# Porsche_Brake_Light.net
KiCad netlist of a schematic drawn in Altium Designer
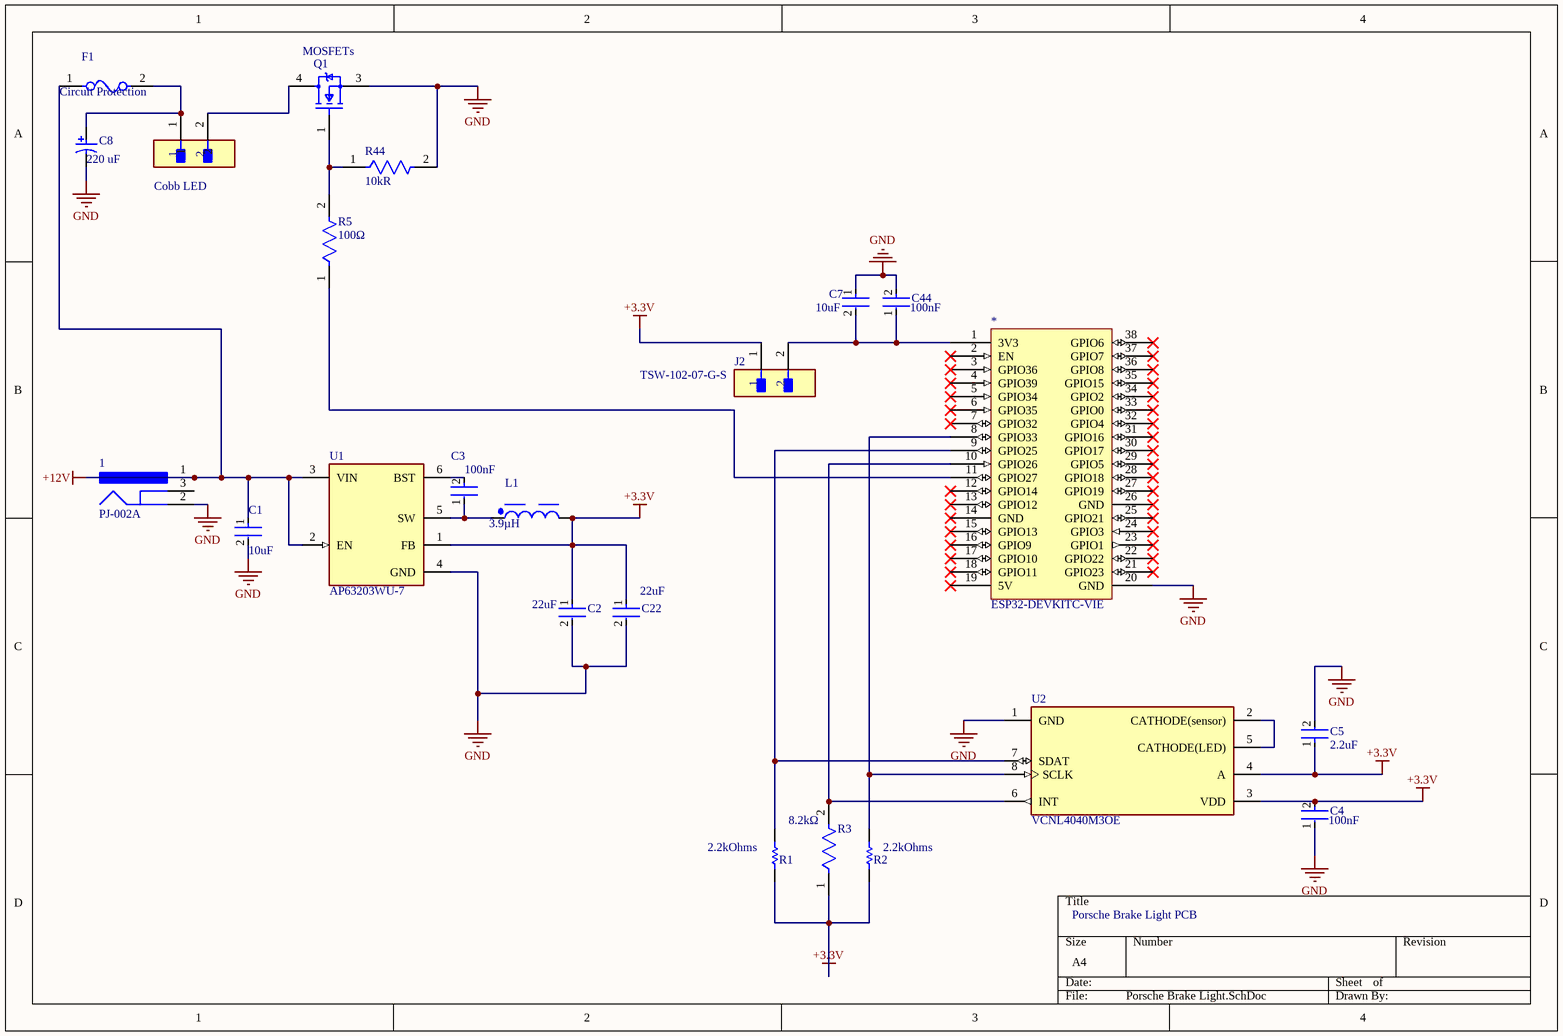
[diagram p0: Porsche Brake Light.SchDoc]

(export (version "E")
  (design (tool "Eeschema 10.0.6"))
  (components
    (comp (ref "*")
      (value "ESP32-DEVKITC-VIE")
      (footprint "ESP32-DEVKITC-VIE-Footprint-1")
      (libsource (lib "Altium DX") (part "ESP32-DEVKITC-VIE-Symbol-1"))
    )
    (comp (ref "1")
      (value "PJ-002A")
      (footprint "CUI-PJ-002A_V")
      (fields (field (name "MANUFACTURER") "CUIInc."))
      (libsource (lib "Altium Content Vault") (part "JACK-2CD3-RN_B"))
    )
    (comp (ref "C1")
      (value "GRM21BR61E106KA73L")
      (footprint "FP-GRM21B-0_15-IPC_C")
      (description "Chip Multilayer Ceramic Capacitors for General Purpose, 0805, 10uF, X5R, 15%, 10%, 25V")
      (fields
        (field (name "VOLTAGE") "25V")
        (field (name "CAPACITANCE") "10uF")
        (field (name "TOLERANCE") "10%")
      )
      (libsource (lib "Altium Content Vault") (part "b4654b650e69147ec39a6b967a45e02"))
    )
    (comp (ref "C2")
      (value "GRM21BZ71A226ME15L")
      (footprint "FP-GRM21B-0_2-e0_2_0_7-IPC_B")
      (description "Chip Multilayer Ceramic Capacitors for General Purpose, 0805, 22uF, X7R, 15%, 20%, 10V")
      (libsource (lib "Altium Content Vault") (part "b4654b650e69147ec39a6b967a45e02"))
    )
    (comp (ref "C3")
      (value "C1608X7R1E104K080AA")
      (footprint "FP-C1608-080-0_1-IPC_B")
      (description "Multilayer Ceramic Capacitors 100nF ±10% 25V X7R SMD 0603")
      (fields
        (field (name "TOLERANCE") "10%")
        (field (name "CAPACITANCE") "100nF")
        (field (name "VOLTAGE") "25V")
      )
      (libsource (lib "Altium Content Vault") (part "236180d848d6139a670b325ea6854c9"))
    )
    (comp (ref "C4")
      (value "C1608X7R1E104K080AA")
      (footprint "FP-C1608-080-0_1-IPC_B")
      (description "Multilayer Ceramic Capacitors 100nF ±10% 25V X7R SMD 0603")
      (fields
        (field (name "TOLERANCE") "10%")
        (field (name "CAPACITANCE") "100nF")
        (field (name "VOLTAGE") "25V")
      )
      (libsource (lib "Altium Content Vault") (part "236180d848d6139a670b325ea6854c9"))
    )
    (comp (ref "C5")
      (value "GRM188R71A225KE15D")
      (footprint "FP-GRM188-0_1-e0_2_0_5-MFG")
      (description "Chip Multilayer Ceramic Capacitors for General Purpose, 0603, 2.2uF, X7R, 15%, 10%, 10V")
      (fields
        (field (name "VOLTAGE") "10V")
        (field (name "CAPACITANCE") "2.2uF")
        (field (name "TOLERANCE") "10%")
      )
      (libsource (lib "Altium Content Vault") (part "11868f565c42a9108669ba33697ecf6"))
    )
    (comp (ref "C7")
      (value "GRM21BR61E106KA73L")
      (footprint "FP-GRM21B-0_15-IPC_C")
      (description "Chip Multilayer Ceramic Capacitors for General Purpose, 0805, 10uF, X5R, 15%, 10%, 25V")
      (fields
        (field (name "VOLTAGE") "25V")
        (field (name "CAPACITANCE") "10uF")
        (field (name "TOLERANCE") "10%")
      )
      (libsource (lib "Altium Content Vault") (part "b4654b650e69147ec39a6b967a45e02"))
    )
    (comp (ref "C8")
      (value "EEE-FK1E221P")
      (footprint "PNSC-EEE-FK1E221P_N")
      (fields (field (name "MANUFACTURER") "Panasonic"))
      (libsource (lib "Altium Content Vault") (part "CAP-P-2"))
    )
    (comp (ref "C22")
      (value "GRM21BZ71A226ME15L")
      (footprint "FP-GRM21B-0_2-e0_2_0_7-IPC_B")
      (description "Chip Multilayer Ceramic Capacitors for General Purpose, 0805, 22uF, X7R, 15%, 20%, 10V")
      (libsource (lib "Altium Content Vault") (part "b4654b650e69147ec39a6b967a45e02"))
    )
    (comp (ref "C44")
      (value "C1608X7R1E104K080AA")
      (footprint "FP-C1608-080-0_1-IPC_B")
      (description "Multilayer Ceramic Capacitors 100nF ±10% 25V X7R SMD 0603")
      (fields
        (field (name "TOLERANCE") "10%")
        (field (name "CAPACITANCE") "100nF")
        (field (name "VOLTAGE") "25V")
      )
      (libsource (lib "Altium Content Vault") (part "236180d848d6139a670b325ea6854c9"))
    )
    (comp (ref "Cobb LED")
      (value "TSW-102-14-G-S")
      (footprint "FP-TSW-102-14-G-S-MFG")
      (description "CONN HEADER VERT 2POS 2.54MM")
      (libsource (lib "Altium Content Vault") (part "88c1139f9d239099ffebecbe3f7647a"))
    )
    (comp (ref "F1")
      (value "TR/3216FF2-R")
      (footprint "FP-3216FF-MFG")
      (description "FUSE BRD MNT 2A 32VAC 63VDC 1206")
      (fields
        (field (name "DEVICE CLASS L1") "Circuit Protection")
        (field (name "MANUFACTURER") "Cooper Bussmann")
        (field (name "OCTOPART") "https://octopart.com/tr%2F3216ff2-r-cooper+bussmann-8723903")
      )
      (libsource (lib "Altium Content Vault") (part "5bcf9b9f640e542cf0359d10258e979"))
    )
    (comp (ref "J2")
      (value "TSW-102-07-G-S")
      (footprint "FP-TSW-102-07-G-S-MFG")
      (description "CONN HEADER VERT 2POS 2.54MM")
      (fields
        (field (name "MANUFACTURER") "Samtec")
        (field (name "OCTOPART") "https://octopart.com/tsw-102-07-g-s-samtec-272197")
      )
      (libsource (lib "Altium Content Vault") (part "3bc925449376181038e59eaffc5286c"))
    )
    (comp (ref "L1")
      (value "74404052039")
      (footprint "WE-LQS_5020")
      (description "Power Inductor, Aec-Q200, 3.9Uh, 2.4A Rohs Compliant: Yes")
      (fields (field (name "TOLERANCE") "30%") (field (name "INDUCTANCE") "3.9µH"))
      (libsource (lib "Altium Content Vault") (part "Inductor - 2"))
    )
    (comp (ref "Q1")
      (value "IRLR7843TRPBF")
      (footprint "FP-PG-TO252-3-MFG")
      (description "MOSFET N-CH 30V 161A DPAK")
      (fields
        (field (name "OCTOPART") "https://octopart.com/irlr7843trpbf-infineon-65875062")
        (field (name "DEVICE CLASS L3") "MOSFETs")
        (field (name "MANUFACTURER") "Infineon")
      )
      (libsource (lib "Altium Content Vault") (part "2f21c11e83d30f418bb422e5a3b3d11"))
    )
    (comp (ref "R1")
      (value "RC0603FR-072K2L")
      (footprint "RESC1608X55X25LL10T15")
      (fields
        (field (name "TOLERANCE") "1%")
        (field (name "RESISTANCE") "2.2kOhms")
        (field (name "MANUFACTURER") "Yageo")
      )
      (libsource (lib "Altium Content Vault") (part "RES-2"))
    )
    (comp (ref "R2")
      (value "RC0603FR-072K2L")
      (footprint "RESC1608X55X25LL10T15")
      (fields
        (field (name "TOLERANCE") "1%")
        (field (name "RESISTANCE") "2.2kOhms")
        (field (name "MANUFACTURER") "Yageo")
      )
      (libsource (lib "Altium Content Vault") (part "RES-2"))
    )
    (comp (ref "R3")
      (value "RC0603FR-078K2L")
      (footprint "FP-RC0603-0_55-MFG")
      (fields (field (name "RESISTANCE") "8.2kΩ") (field (name "TOLERANCE") "1%"))
      (libsource (lib "Altium Content Vault") (part "1029c3af85768c4190bb7ad29bc67b5"))
    )
    (comp (ref "R5")
      (value "RC0603FR-07100RL")
      (footprint "FP-RC0603-0_55-MFG")
      (fields (field (name "TOLERANCE") "1%") (field (name "RESISTANCE") "100Ω"))
      (libsource (lib "Altium Content Vault") (part "1029c3af85768c4190bb7ad29bc67b5"))
    )
    (comp (ref "R44")
      (value "RC0603FR-0710KL")
      (footprint "FP-RC0603-0_55-IPC_C")
      (description "RES 10K OHM 1% 1/10W 0603")
      (fields (field (name "TOLERANCE") "1%") (field (name "RESISTANCE") "10kR"))
      (libsource (lib "Altium Content Vault") (part "1029c3af85768c4190bb7ad29bc67b5"))
    )
    (comp (ref "U1")
      (value "AP63203WU-7")
      (footprint "FP-TSOT26-MFG")
      (description "IC REG BUCK 3.3V 2A TSOT26")
      (fields
        (field (name "MANUFACTURER") "Diodes Inc.")
        (field (name "OCTOPART") "https://octopart.com/ap63203wu-7-diodes+inc.-98099550")
      )
      (libsource (lib "Altium Content Vault") (part "0e61c2974d7114b43f01ef96ae2e524"))
    )
    (comp (ref "U2")
      (value "VCNL4040M3OE")
      (footprint "FP-VCNL4040M3OE-MFG")
      (description "SENSOR OPT 550NM AMBIENT 8SMD")
      (fields
        (field (name "MANUFACTURER") "Vishay")
        (field (name "OCTOPART") "https://octopart.com/vcnl4040m3oe-vishay-56243155")
      )
      (libsource (lib "Altium Content Vault") (part "6d64fb2289e8624d322eaf5b536817e"))
    )
  )
  (nets
    (net (code "1") (name "+3.3V") (class "Default")
      (node (ref "C2") (pin "1") (pinfunction "1_1") (pintype "passive"))
      (node (ref "C22") (pin "1") (pinfunction "1_1") (pintype "passive"))
      (node (ref "C4") (pin "2") (pinfunction "2_2") (pintype "passive"))
      (node (ref "C5") (pin "1") (pinfunction "1_1") (pintype "passive"))
      (node (ref "J2") (pin "1") (pinfunction "1_1") (pintype "passive"))
      (node (ref "L1") (pin "2") (pinfunction "2_2") (pintype "passive"))
      (node (ref "R1") (pin "1") (pinfunction "1_1") (pintype "passive"))
      (node (ref "R2") (pin "1") (pinfunction "1_1") (pintype "passive"))
      (node (ref "R3") (pin "1") (pinfunction "1_1") (pintype "passive"))
      (node (ref "U1") (pin "1") (pinfunction "FB_1") (pintype "passive"))
      (node (ref "U2") (pin "3") (pinfunction "VDD_3") (pintype "power_in"))
      (node (ref "U2") (pin "4") (pinfunction "A_4") (pintype "passive"))
    )
    (net (code "2") (name "+12V") (class "Default")
      (node (ref "1") (pin "1") (pinfunction "1_1") (pintype "passive"))
      (node (ref "C1") (pin "1") (pinfunction "1_1") (pintype "passive"))
      (node (ref "F1") (pin "1") (pinfunction "1_1") (pintype "passive"))
      (node (ref "U1") (pin "2") (pinfunction "EN_2") (pintype "input"))
      (node (ref "U1") (pin "3") (pinfunction "VIN_3") (pintype "power_in"))
    )
    (net (code "3") (name "GND") (class "Default")
      (node (ref "*") (pin "20") (pinfunction "GND_20") (pintype "power_in"))
      (node (ref "1") (pin "2") (pinfunction "2_2") (pintype "passive"))
      (node (ref "C1") (pin "2") (pinfunction "2_2") (pintype "passive"))
      (node (ref "C2") (pin "2") (pinfunction "2_2") (pintype "passive"))
      (node (ref "C22") (pin "2") (pinfunction "2_2") (pintype "passive"))
      (node (ref "C4") (pin "1") (pinfunction "1_1") (pintype "passive"))
      (node (ref "C44") (pin "2") (pinfunction "2_2") (pintype "passive"))
      (node (ref "C5") (pin "2") (pinfunction "2_2") (pintype "passive"))
      (node (ref "C7") (pin "1") (pinfunction "1_1") (pintype "passive"))
      (node (ref "C8") (pin "2") (pinfunction "2_2") (pintype "passive"))
      (node (ref "Q1") (pin "3") (pinfunction "SOURCE_3") (pintype "passive"))
      (node (ref "R44") (pin "2") (pinfunction "2_2") (pintype "passive"))
      (node (ref "U1") (pin "4") (pinfunction "GND_4") (pintype "power_in"))
      (node (ref "U2") (pin "1") (pinfunction "GND_1") (pintype "power_in"))
    )
    (net (code "4") (name "Net-(*-3V3)") (class "Default")
      (node (ref "*") (pin "1") (pinfunction "3V3_1") (pintype "power_in"))
      (node (ref "C44") (pin "1") (pinfunction "1_1") (pintype "passive"))
      (node (ref "C7") (pin "2") (pinfunction "2_2") (pintype "passive"))
      (node (ref "J2") (pin "2") (pinfunction "2_2") (pintype "power_in"))
    )
    (net (code "5") (name "Net-(*-GPIO25)") (class "Default")
      (node (ref "*") (pin "9") (pinfunction "GPIO25_9") (pintype "bidirectional"))
      (node (ref "R1") (pin "2") (pinfunction "2_2") (pintype "passive"))
      (node (ref "U2") (pin "7") (pinfunction "SDAT_7") (pintype "bidirectional"))
    )
    (net (code "6") (name "Net-(*-GPIO26)") (class "Default")
      (node (ref "*") (pin "10") (pinfunction "GPIO26_10") (pintype "input"))
      (node (ref "R3") (pin "2") (pinfunction "2_2") (pintype "passive"))
      (node (ref "U2") (pin "6") (pinfunction "INT_6") (pintype "output"))
    )
    (net (code "7") (name "Net-(*-GPIO27)") (class "Default")
      (node (ref "*") (pin "11") (pinfunction "GPIO27_11") (pintype "bidirectional"))
      (node (ref "R5") (pin "1") (pinfunction "1_1") (pintype "passive"))
    )
    (net (code "8") (name "Net-(*-GPIO33)") (class "Default")
      (node (ref "*") (pin "8") (pinfunction "GPIO33_8") (pintype "bidirectional"))
      (node (ref "R2") (pin "2") (pinfunction "2_2") (pintype "passive"))
      (node (ref "U2") (pin "8") (pinfunction "SCLK_8") (pintype "input"))
    )
    (net (code "9") (name "Net-(C8-Pad1)") (class "Default")
      (node (ref "C8") (pin "1") (pinfunction "1_1") (pintype "passive"))
      (node (ref "Cobb LED") (pin "1") (pinfunction "1_1") (pintype "passive"))
      (node (ref "F1") (pin "2") (pinfunction "2_2") (pintype "passive"))
    )
    (net (code "10") (name "Net-(Q1-DRAIN)") (class "Default")
      (node (ref "Cobb LED") (pin "2") (pinfunction "2_2") (pintype "passive"))
      (node (ref "Q1") (pin "4") (pinfunction "DRAIN_4") (pintype "passive"))
    )
    (net (code "11") (name "Net-(Q1-GATE)") (class "Default")
      (node (ref "Q1") (pin "1") (pinfunction "GATE_1") (pintype "passive"))
      (node (ref "R44") (pin "1") (pinfunction "1_1") (pintype "passive"))
      (node (ref "R5") (pin "2") (pinfunction "2_2") (pintype "passive"))
    )
    (net (code "12") (name "Net-(U1-BST)") (class "Default")
      (node (ref "C3") (pin "2") (pinfunction "2_2") (pintype "passive"))
      (node (ref "U1") (pin "6") (pinfunction "BST_6") (pintype "passive"))
    )
    (net (code "13") (name "Net-(U1-SW)") (class "Default")
      (node (ref "C3") (pin "1") (pinfunction "1_1") (pintype "passive"))
      (node (ref "L1") (pin "1") (pinfunction "1_1") (pintype "passive"))
      (node (ref "U1") (pin "5") (pinfunction "SW_5") (pintype "passive"))
    )
    (net (code "14") (name "Net-(U2-CATHODE(LED))") (class "Default")
      (node (ref "U2") (pin "2") (pinfunction "CATHODE(sensor)_2") (pintype "passive"))
      (node (ref "U2") (pin "5") (pinfunction "CATHODE(LED)_5") (pintype "passive"))
    )
    (net (code "15") (name "unconnected-(*-5V-Pad19)") (class "Default")
      (node (ref "*") (pin "19") (pinfunction "5V_19") (pintype "power_in+no_connect"))
    )
    (net (code "16") (name "unconnected-(*-EN-Pad2)") (class "Default")
      (node (ref "*") (pin "2") (pinfunction "EN_2") (pintype "input+no_connect"))
    )
    (net (code "17") (name "unconnected-(*-GND-Pad14)") (class "Default")
      (node (ref "*") (pin "14") (pinfunction "GND_14") (pintype "power_in+no_connect"))
    )
    (net (code "18") (name "unconnected-(*-GND-Pad26)") (class "Default")
      (node (ref "*") (pin "26") (pinfunction "GND_26") (pintype "power_in+no_connect"))
    )
    (net (code "19") (name "unconnected-(*-GPIO0-Pad33)") (class "Default")
      (node (ref "*") (pin "33") (pinfunction "GPIO0_33") (pintype "bidirectional+no_connect"))
    )
    (net (code "20") (name "unconnected-(*-GPIO1-Pad23)") (class "Default")
      (node (ref "*") (pin "23") (pinfunction "GPIO1_23") (pintype "output+no_connect"))
    )
    (net (code "21") (name "unconnected-(*-GPIO2-Pad34)") (class "Default")
      (node (ref "*") (pin "34") (pinfunction "GPIO2_34") (pintype "bidirectional+no_connect"))
    )
    (net (code "22") (name "unconnected-(*-GPIO3-Pad24)") (class "Default")
      (node (ref "*") (pin "24") (pinfunction "GPIO3_24") (pintype "input+no_connect"))
    )
    (net (code "23") (name "unconnected-(*-GPIO4-Pad32)") (class "Default")
      (node (ref "*") (pin "32") (pinfunction "GPIO4_32") (pintype "bidirectional+no_connect"))
    )
    (net (code "24") (name "unconnected-(*-GPIO5-Pad29)") (class "Default")
      (node (ref "*") (pin "29") (pinfunction "GPIO5_29") (pintype "bidirectional+no_connect"))
    )
    (net (code "25") (name "unconnected-(*-GPIO6-Pad38)") (class "Default")
      (node (ref "*") (pin "38") (pinfunction "GPIO6_38") (pintype "bidirectional+no_connect"))
    )
    (net (code "26") (name "unconnected-(*-GPIO7-Pad37)") (class "Default")
      (node (ref "*") (pin "37") (pinfunction "GPIO7_37") (pintype "bidirectional+no_connect"))
    )
    (net (code "27") (name "unconnected-(*-GPIO8-Pad36)") (class "Default")
      (node (ref "*") (pin "36") (pinfunction "GPIO8_36") (pintype "bidirectional+no_connect"))
    )
    (net (code "28") (name "unconnected-(*-GPIO9-Pad16)") (class "Default")
      (node (ref "*") (pin "16") (pinfunction "GPIO9_16") (pintype "bidirectional+no_connect"))
    )
    (net (code "29") (name "unconnected-(*-GPIO10-Pad17)") (class "Default")
      (node (ref "*") (pin "17") (pinfunction "GPIO10_17") (pintype "bidirectional+no_connect"))
    )
    (net (code "30") (name "unconnected-(*-GPIO11-Pad18)") (class "Default")
      (node (ref "*") (pin "18") (pinfunction "GPIO11_18") (pintype "bidirectional+no_connect"))
    )
    (net (code "31") (name "unconnected-(*-GPIO12-Pad13)") (class "Default")
      (node (ref "*") (pin "13") (pinfunction "GPIO12_13") (pintype "bidirectional+no_connect"))
    )
    (net (code "32") (name "unconnected-(*-GPIO13-Pad15)") (class "Default")
      (node (ref "*") (pin "15") (pinfunction "GPIO13_15") (pintype "bidirectional+no_connect"))
    )
    (net (code "33") (name "unconnected-(*-GPIO14-Pad12)") (class "Default")
      (node (ref "*") (pin "12") (pinfunction "GPIO14_12") (pintype "bidirectional+no_connect"))
    )
    (net (code "34") (name "unconnected-(*-GPIO15-Pad35)") (class "Default")
      (node (ref "*") (pin "35") (pinfunction "GPIO15_35") (pintype "bidirectional+no_connect"))
    )
    (net (code "35") (name "unconnected-(*-GPIO16-Pad31)") (class "Default")
      (node (ref "*") (pin "31") (pinfunction "GPIO16_31") (pintype "bidirectional+no_connect"))
    )
    (net (code "36") (name "unconnected-(*-GPIO17-Pad30)") (class "Default")
      (node (ref "*") (pin "30") (pinfunction "GPIO17_30") (pintype "bidirectional+no_connect"))
    )
    (net (code "37") (name "unconnected-(*-GPIO18-Pad28)") (class "Default")
      (node (ref "*") (pin "28") (pinfunction "GPIO18_28") (pintype "bidirectional+no_connect"))
    )
    (net (code "38") (name "unconnected-(*-GPIO19-Pad27)") (class "Default")
      (node (ref "*") (pin "27") (pinfunction "GPIO19_27") (pintype "bidirectional+no_connect"))
    )
    (net (code "39") (name "unconnected-(*-GPIO21-Pad25)") (class "Default")
      (node (ref "*") (pin "25") (pinfunction "GPIO21_25") (pintype "bidirectional+no_connect"))
    )
    (net (code "40") (name "unconnected-(*-GPIO22-Pad22)") (class "Default")
      (node (ref "*") (pin "22") (pinfunction "GPIO22_22") (pintype "bidirectional+no_connect"))
    )
    (net (code "41") (name "unconnected-(*-GPIO23-Pad21)") (class "Default")
      (node (ref "*") (pin "21") (pinfunction "GPIO23_21") (pintype "bidirectional+no_connect"))
    )
    (net (code "42") (name "unconnected-(*-GPIO32-Pad7)") (class "Default")
      (node (ref "*") (pin "7") (pinfunction "GPIO32_7") (pintype "bidirectional+no_connect"))
    )
    (net (code "43") (name "unconnected-(*-GPIO34-Pad5)") (class "Default")
      (node (ref "*") (pin "5") (pinfunction "GPIO34_5") (pintype "input+no_connect"))
    )
    (net (code "44") (name "unconnected-(*-GPIO35-Pad6)") (class "Default")
      (node (ref "*") (pin "6") (pinfunction "GPIO35_6") (pintype "input+no_connect"))
    )
    (net (code "45") (name "unconnected-(*-GPIO36-Pad3)") (class "Default")
      (node (ref "*") (pin "3") (pinfunction "GPIO36_3") (pintype "input+no_connect"))
    )
    (net (code "46") (name "unconnected-(*-GPIO39-Pad4)") (class "Default")
      (node (ref "*") (pin "4") (pinfunction "GPIO39_4") (pintype "input+no_connect"))
    )
    (net (code "47") (name "unconnected-(1-Pad3)") (class "Default")
      (node (ref "1") (pin "3") (pinfunction "3_3") (pintype "passive"))
    )
  )
)
